# rev02_14.net
KiCad netlist of a schematic drawn in Altium Designer
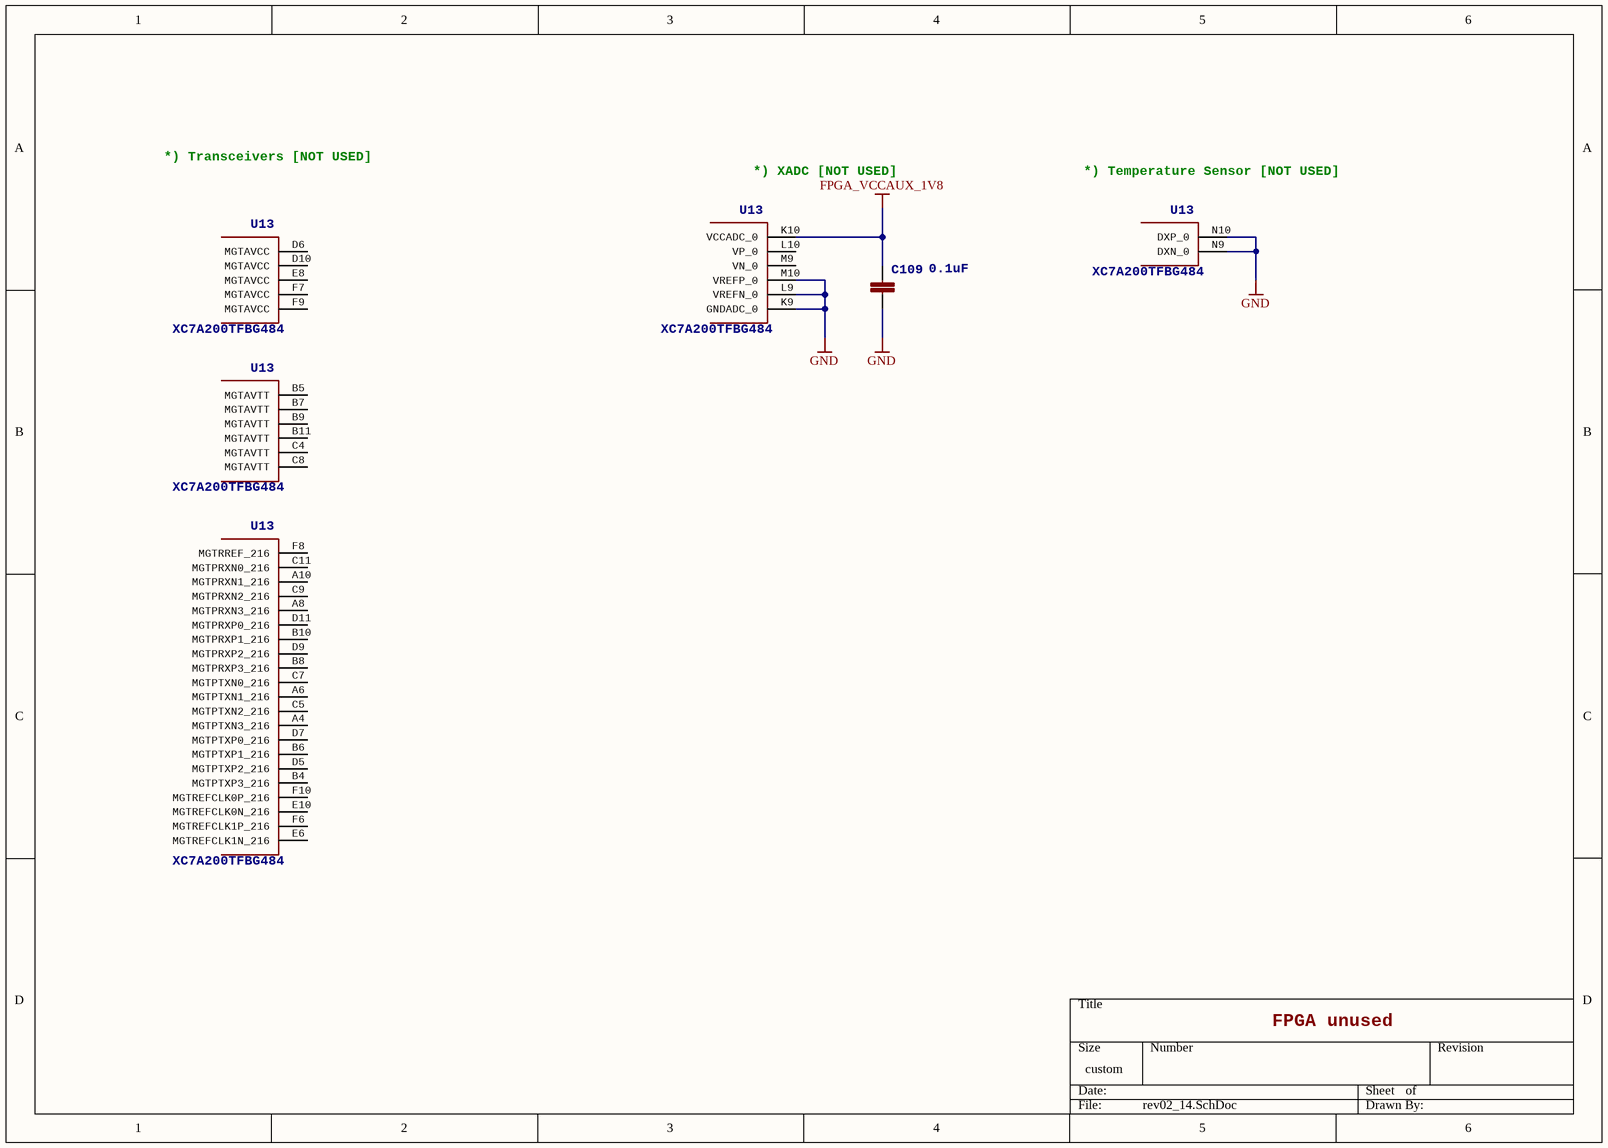
[diagram p0: rev02_14.SchDoc]

(export (version "E")
  (design (tool "Eeschema 10.0.6"))
  (components
    (comp (ref "C109")
      (value "0.1uF")
      (footprint "C_0402")
      (description "0402 CAPACITOR")
      (fields (field (name "TOLERANCE") "10%") (field (name ">NAME") "C109"))
      (libsource (lib "resistor") (part "C-EUC0402"))
    )
    (comp (ref "U13")
      (value "XC7A200TFBG484")
      (footprint "BGA484C100P22X22_2300X2300X254")
      (description "Xilinx FPGA: XC7A200TFBG484")
      (fields
        (field (name "MFR") "Xilinx")
        (field (name "MPN") "XC7A200T-1FBG484C")
        (field (name ">NAME") "U13")
        (field (name ">VALUE") "XC7A200TFBG484")
      )
      (libsource (lib "Xilinx_XC7A200TFBG484") (part "XC7A200TFBG484"))
    )
  )
  (nets
    (net (code "1") (name "FPGA_VCCAUX_1V8") (class "Default")
      (node (ref "C109") (pin "1") (pinfunction "1_1") (pintype "passive"))
      (node (ref "U13") (pin "K10") (pinfunction "VCCADC_0_K10") (pintype "passive"))
    )
    (net (code "2") (name "GND") (class "Default")
      (node (ref "C109") (pin "2") (pinfunction "2_2") (pintype "passive"))
      (node (ref "U13") (pin "K9") (pinfunction "GNDADC_0_K9") (pintype "passive"))
      (node (ref "U13") (pin "L9") (pinfunction "VREFN_0_L9") (pintype "passive"))
      (node (ref "U13") (pin "M10") (pinfunction "VREFP_0_M10") (pintype "passive"))
      (node (ref "U13") (pin "N10") (pinfunction "DXP_0_N10") (pintype "passive"))
      (node (ref "U13") (pin "N9") (pinfunction "DXN_0_N9") (pintype "passive"))
    )
    (net (code "3") (name "unconnected-(U13H-MGTPRXN0_216-PadC11)") (class "Default")
      (node (ref "U13") (pin "C11") (pinfunction "MGTPRXN0_216_C11") (pintype "passive"))
    )
    (net (code "4") (name "unconnected-(U13H-MGTPRXN1_216-PadA10)") (class "Default")
      (node (ref "U13") (pin "A10") (pinfunction "MGTPRXN1_216_A10") (pintype "passive"))
    )
    (net (code "5") (name "unconnected-(U13H-MGTPRXN2_216-PadC9)") (class "Default")
      (node (ref "U13") (pin "C9") (pinfunction "MGTPRXN2_216_C9") (pintype "passive"))
    )
    (net (code "6") (name "unconnected-(U13H-MGTPRXN3_216-PadA8)") (class "Default")
      (node (ref "U13") (pin "A8") (pinfunction "MGTPRXN3_216_A8") (pintype "passive"))
    )
    (net (code "7") (name "unconnected-(U13H-MGTPRXP0_216-PadD11)") (class "Default")
      (node (ref "U13") (pin "D11") (pinfunction "MGTPRXP0_216_D11") (pintype "passive"))
    )
    (net (code "8") (name "unconnected-(U13H-MGTPRXP1_216-PadB10)") (class "Default")
      (node (ref "U13") (pin "B10") (pinfunction "MGTPRXP1_216_B10") (pintype "passive"))
    )
    (net (code "9") (name "unconnected-(U13H-MGTPRXP2_216-PadD9)") (class "Default")
      (node (ref "U13") (pin "D9") (pinfunction "MGTPRXP2_216_D9") (pintype "passive"))
    )
    (net (code "10") (name "unconnected-(U13H-MGTPRXP3_216-PadB8)") (class "Default")
      (node (ref "U13") (pin "B8") (pinfunction "MGTPRXP3_216_B8") (pintype "passive"))
    )
    (net (code "11") (name "unconnected-(U13H-MGTPTXN0_216-PadC7)") (class "Default")
      (node (ref "U13") (pin "C7") (pinfunction "MGTPTXN0_216_C7") (pintype "passive"))
    )
    (net (code "12") (name "unconnected-(U13H-MGTPTXN1_216-PadA6)") (class "Default")
      (node (ref "U13") (pin "A6") (pinfunction "MGTPTXN1_216_A6") (pintype "passive"))
    )
    (net (code "13") (name "unconnected-(U13H-MGTPTXN2_216-PadC5)") (class "Default")
      (node (ref "U13") (pin "C5") (pinfunction "MGTPTXN2_216_C5") (pintype "passive"))
    )
    (net (code "14") (name "unconnected-(U13H-MGTPTXN3_216-PadA4)") (class "Default")
      (node (ref "U13") (pin "A4") (pinfunction "MGTPTXN3_216_A4") (pintype "passive"))
    )
    (net (code "15") (name "unconnected-(U13H-MGTPTXP0_216-PadD7)") (class "Default")
      (node (ref "U13") (pin "D7") (pinfunction "MGTPTXP0_216_D7") (pintype "passive"))
    )
    (net (code "16") (name "unconnected-(U13H-MGTPTXP1_216-PadB6)") (class "Default")
      (node (ref "U13") (pin "B6") (pinfunction "MGTPTXP1_216_B6") (pintype "passive"))
    )
    (net (code "17") (name "unconnected-(U13H-MGTPTXP2_216-PadD5)") (class "Default")
      (node (ref "U13") (pin "D5") (pinfunction "MGTPTXP2_216_D5") (pintype "passive"))
    )
    (net (code "18") (name "unconnected-(U13H-MGTPTXP3_216-PadB4)") (class "Default")
      (node (ref "U13") (pin "B4") (pinfunction "MGTPTXP3_216_B4") (pintype "passive"))
    )
    (net (code "19") (name "unconnected-(U13H-MGTREFCLK0N_216-PadE10)") (class "Default")
      (node (ref "U13") (pin "E10") (pinfunction "MGTREFCLK0N_216_E10") (pintype "passive"))
    )
    (net (code "20") (name "unconnected-(U13H-MGTREFCLK0P_216-PadF10)") (class "Default")
      (node (ref "U13") (pin "F10") (pinfunction "MGTREFCLK0P_216_F10") (pintype "passive"))
    )
    (net (code "21") (name "unconnected-(U13H-MGTREFCLK1N_216-PadE6)") (class "Default")
      (node (ref "U13") (pin "E6") (pinfunction "MGTREFCLK1N_216_E6") (pintype "passive"))
    )
    (net (code "22") (name "unconnected-(U13H-MGTREFCLK1P_216-PadF6)") (class "Default")
      (node (ref "U13") (pin "F6") (pinfunction "MGTREFCLK1P_216_F6") (pintype "passive"))
    )
    (net (code "23") (name "unconnected-(U13H-MGTRREF_216-PadF8)") (class "Default")
      (node (ref "U13") (pin "F8") (pinfunction "MGTRREF_216_F8") (pintype "passive"))
    )
    (net (code "24") (name "unconnected-(U13K-MGTAVCC-PadD6)") (class "Default")
      (node (ref "U13") (pin "D6") (pinfunction "MGTAVCC_D6") (pintype "passive"))
    )
    (net (code "25") (name "unconnected-(U13K-MGTAVCC-PadD10)") (class "Default")
      (node (ref "U13") (pin "D10") (pinfunction "MGTAVCC_D10") (pintype "passive"))
    )
    (net (code "26") (name "unconnected-(U13K-MGTAVCC-PadE8)") (class "Default")
      (node (ref "U13") (pin "E8") (pinfunction "MGTAVCC_E8") (pintype "passive"))
    )
    (net (code "27") (name "unconnected-(U13K-MGTAVCC-PadF7)") (class "Default")
      (node (ref "U13") (pin "F7") (pinfunction "MGTAVCC_F7") (pintype "passive"))
    )
    (net (code "28") (name "unconnected-(U13K-MGTAVCC-PadF9)") (class "Default")
      (node (ref "U13") (pin "F9") (pinfunction "MGTAVCC_F9") (pintype "passive"))
    )
    (net (code "29") (name "unconnected-(U13L-MGTAVTT-PadB5)") (class "Default")
      (node (ref "U13") (pin "B5") (pinfunction "MGTAVTT_B5") (pintype "passive"))
    )
    (net (code "30") (name "unconnected-(U13L-MGTAVTT-PadB7)") (class "Default")
      (node (ref "U13") (pin "B7") (pinfunction "MGTAVTT_B7") (pintype "passive"))
    )
    (net (code "31") (name "unconnected-(U13L-MGTAVTT-PadB9)") (class "Default")
      (node (ref "U13") (pin "B9") (pinfunction "MGTAVTT_B9") (pintype "passive"))
    )
    (net (code "32") (name "unconnected-(U13L-MGTAVTT-PadB11)") (class "Default")
      (node (ref "U13") (pin "B11") (pinfunction "MGTAVTT_B11") (pintype "passive"))
    )
    (net (code "33") (name "unconnected-(U13L-MGTAVTT-PadC4)") (class "Default")
      (node (ref "U13") (pin "C4") (pinfunction "MGTAVTT_C4") (pintype "passive"))
    )
    (net (code "34") (name "unconnected-(U13L-MGTAVTT-PadC8)") (class "Default")
      (node (ref "U13") (pin "C8") (pinfunction "MGTAVTT_C8") (pintype "passive"))
    )
    (net (code "35") (name "unconnected-(U13Q-VN_0-PadM9)") (class "Default")
      (node (ref "U13") (pin "M9") (pinfunction "VN_0_M9") (pintype "passive"))
    )
    (net (code "36") (name "unconnected-(U13Q-VP_0-PadL10)") (class "Default")
      (node (ref "U13") (pin "L10") (pinfunction "VP_0_L10") (pintype "passive"))
    )
  )
)
